# tumki_bot1_vib_sens_driv.net
KiCad netlist of a schematic drawn in EasyEDA Pro
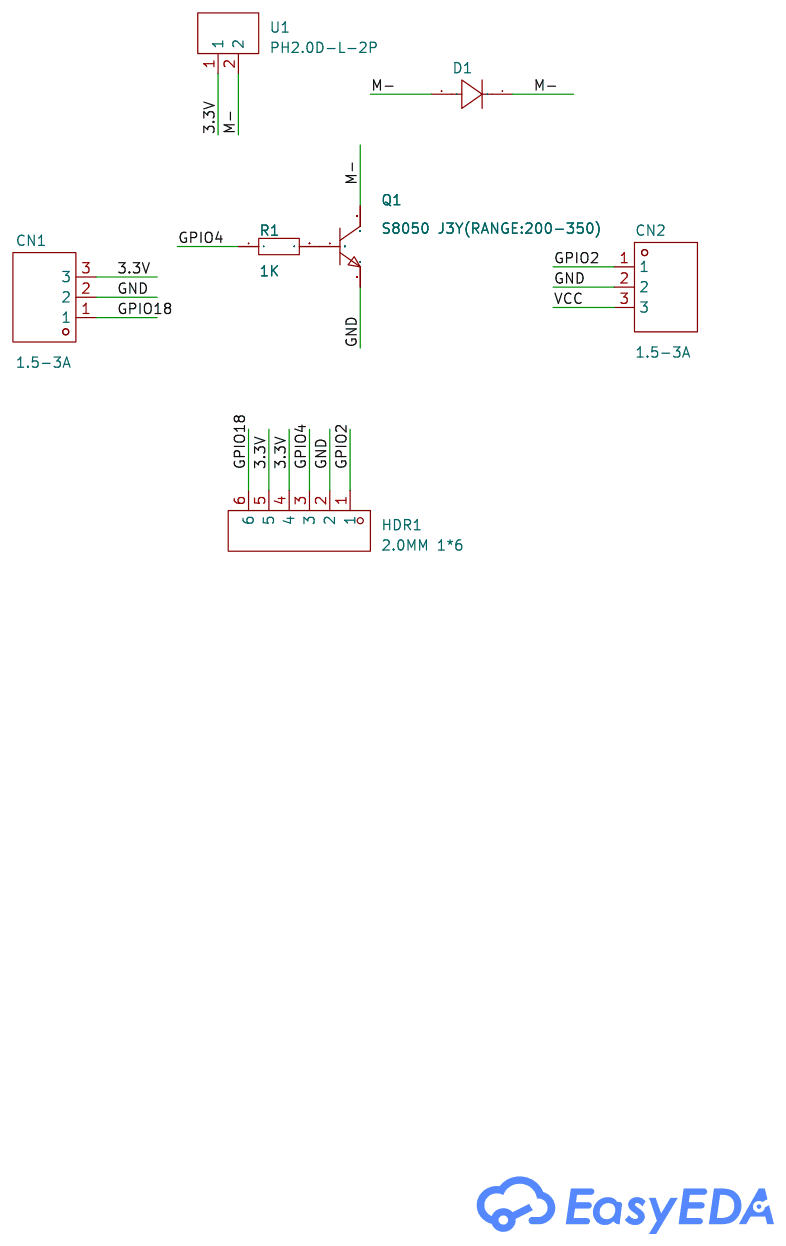
[diagram p0: schematic sheet]

(export (version "E")
  (design (tool "Eeschema 10.0.6"))
  (components
    (comp (ref "CN1")
      (value "1.5-3A")
      (footprint "easyedapro:CONN-TH_3P-P1.50_ZH-3A")
      (libsource (lib "easyedapro") (part "1.5-3A"))
    )
    (comp (ref "CN2")
      (value "1.5-3A")
      (footprint "easyedapro:CONN-TH_3P-P1.50_ZH-3A")
      (libsource (lib "easyedapro") (part "1.5-3A"))
    )
    (comp (ref "D1")
      (value "~")
      (footprint "easyedapro:SMA_L4.4-W2.8-LS5.4-RD")
      (libsource (lib "easyedapro") (part "D_1N4007"))
    )
    (comp (ref "HDR1")
      (value "2.0MM 1*6")
      (footprint "easyedapro:HDR-TH_6P-P2.00-V-F")
      (libsource (lib "easyedapro") (part "2.0MM 1*6"))
    )
    (comp (ref "Q1")
      (value "S8050 J3Y(RANGE:200-350)")
      (footprint "easyedapro:SOT-23-3_L3.0-W1.7-P0.95-LS2.9-BR")
      (fields (field (name "Manufacturer") "CJ(江苏长电/长晶)"))
      (libsource (lib "easyedapro") (part "S8050_C2146"))
    )
    (comp (ref "R1") (value "10K") (footprint "easyedapro:R0603") (libsource (lib "easyedapro") (part "Res")))
    (comp (ref "U1")
      (value "PH2.0D-L-2P")
      (footprint "easyedapro:CONN-TH_PH-2A_C2908623")
      (libsource (lib "easyedapro") (part "PH2.0D-L-2P"))
    )
  )
  (nets
    (net (code "1") (name "/3.3V") (class "Default")
      (node (ref "CN1") (pin "3") (pinfunction "3_3") (pintype "unspecified"))
      (node (ref "HDR1") (pin "4") (pinfunction "4_4") (pintype "input"))
      (node (ref "HDR1") (pin "5") (pinfunction "5_5") (pintype "input"))
      (node (ref "U1") (pin "1") (pinfunction "1_1") (pintype "unspecified"))
    )
    (net (code "2") (name "/GND") (class "Default")
      (node (ref "CN1") (pin "2") (pinfunction "2_2") (pintype "unspecified"))
      (node (ref "CN2") (pin "2") (pinfunction "2_2") (pintype "unspecified"))
      (node (ref "HDR1") (pin "2") (pinfunction "2_2") (pintype "input"))
      (node (ref "Q1") (pin "2") (pinfunction "E_2") (pintype "unspecified"))
    )
    (net (code "3") (name "/GPIO2") (class "Default")
      (node (ref "CN2") (pin "1") (pinfunction "1_1") (pintype "unspecified"))
      (node (ref "HDR1") (pin "1") (pinfunction "1_1") (pintype "input"))
    )
    (net (code "4") (name "/GPIO4") (class "Default")
      (node (ref "HDR1") (pin "3") (pinfunction "3_3") (pintype "input"))
      (node (ref "R1") (pin "1") (pinfunction "1_1") (pintype "input"))
    )
    (net (code "5") (name "/GPIO18") (class "Default")
      (node (ref "CN1") (pin "1") (pinfunction "1_1") (pintype "unspecified"))
      (node (ref "HDR1") (pin "6") (pinfunction "6_6") (pintype "input"))
    )
    (net (code "6") (name "/M-") (class "Default")
      (node (ref "D1") (pin "1") (pinfunction "K_1") (pintype "input"))
      (node (ref "D1") (pin "2") (pinfunction "A_2") (pintype "input"))
      (node (ref "Q1") (pin "3") (pinfunction "C_3") (pintype "unspecified"))
      (node (ref "U1") (pin "2") (pinfunction "2_2") (pintype "unspecified"))
    )
    (net (code "7") (name "/VCC") (class "Default")
      (node (ref "CN2") (pin "3") (pinfunction "3_3") (pintype "unspecified"))
    )
    (net (code "8") (name "Net-(Q1-B)") (class "Default")
      (node (ref "Q1") (pin "1") (pinfunction "B_1") (pintype "unspecified"))
      (node (ref "R1") (pin "2") (pinfunction "2_2") (pintype "input"))
    )
  )
)
